# NRF52840-Beacon-V-1-3.net
KiCad netlist of a schematic drawn in Altium Designer
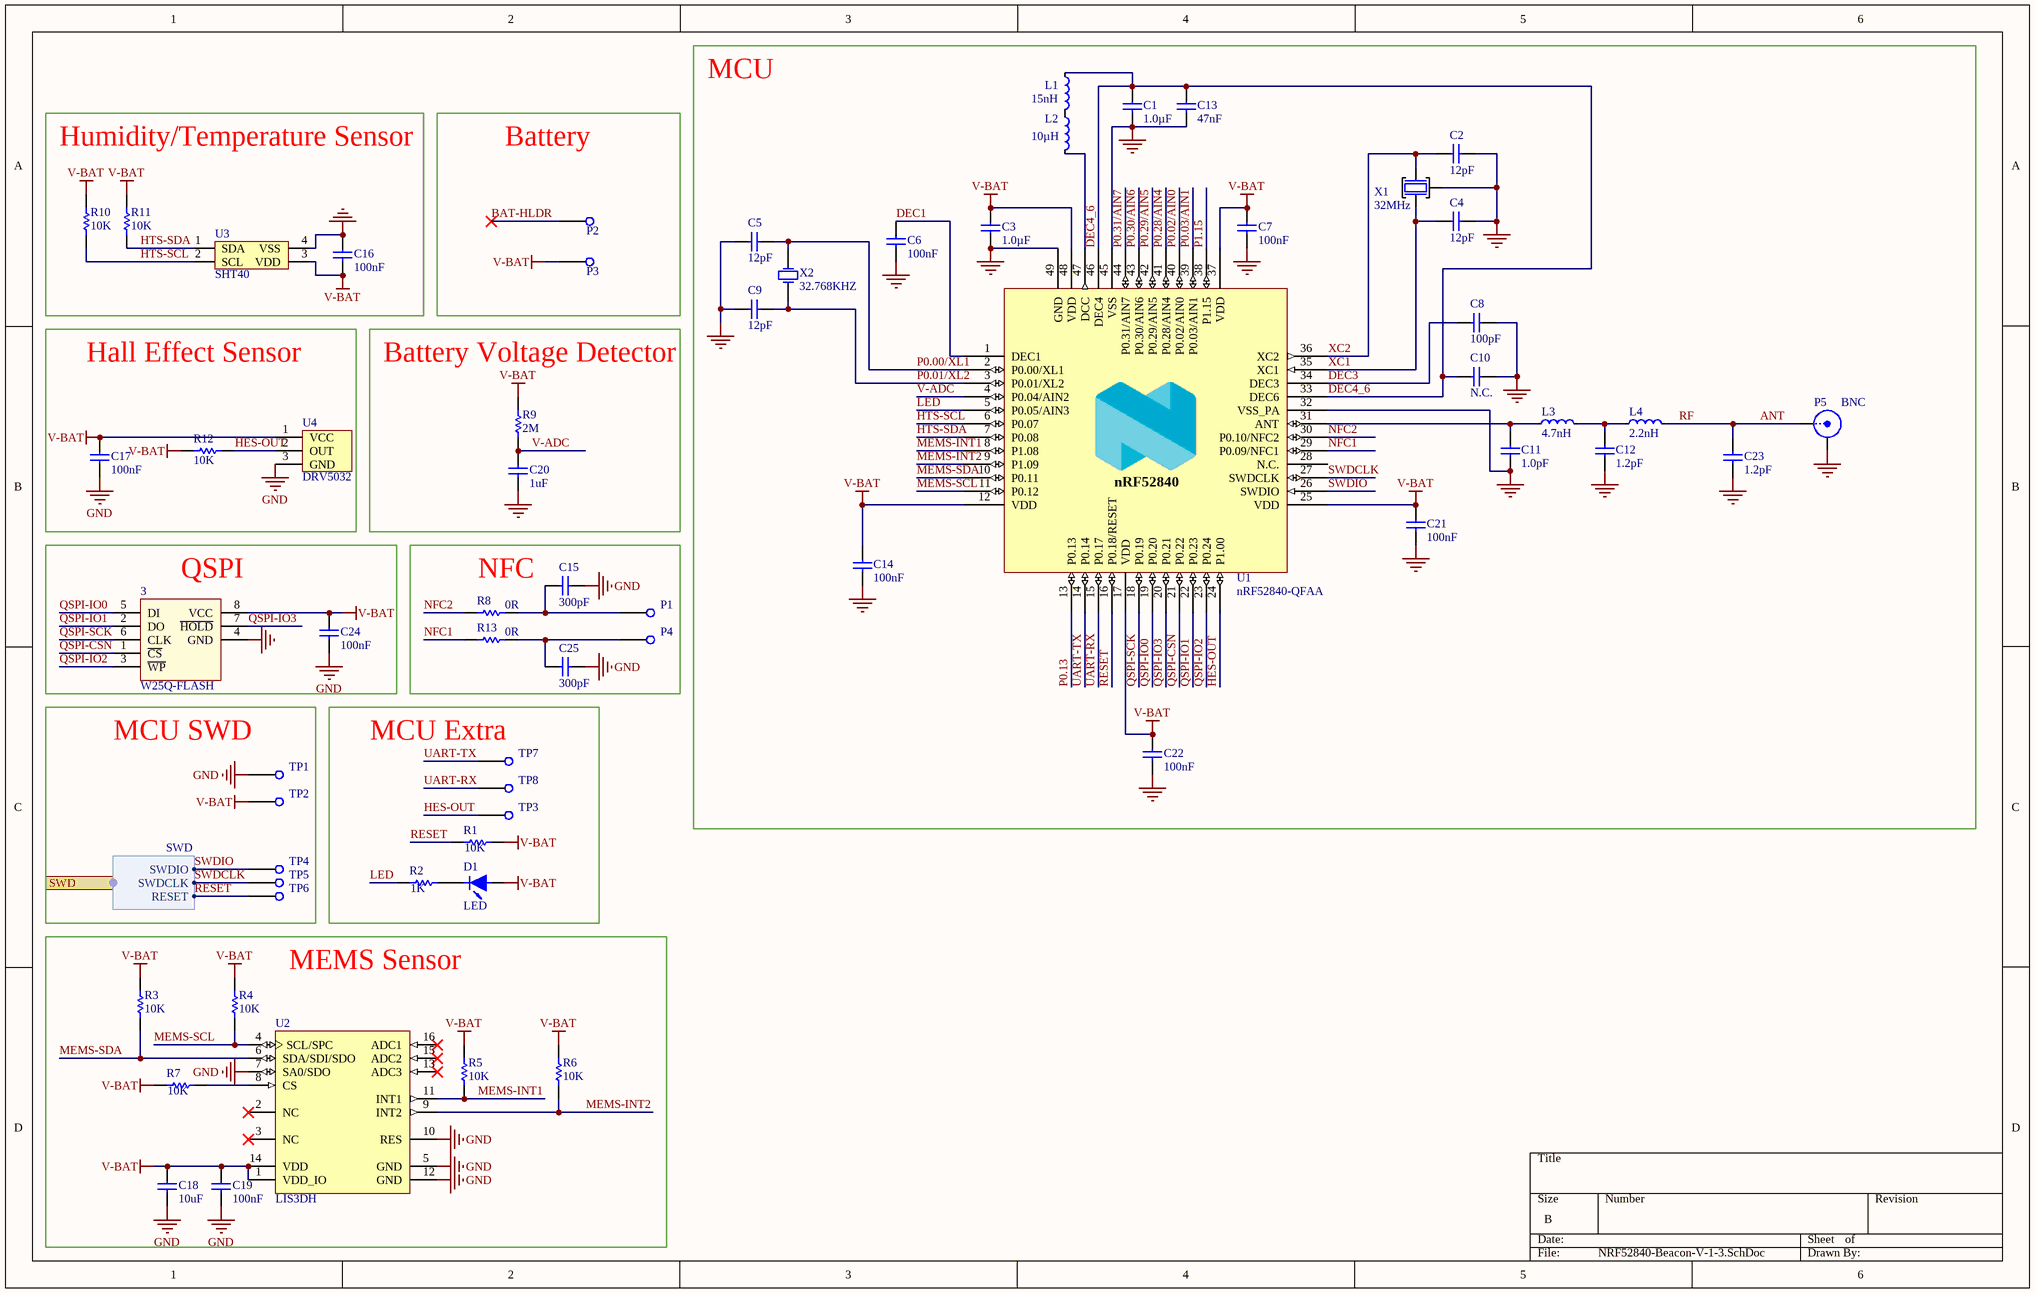
[diagram p0: NRF52840-Beacon-V-1-3.SchDoc]

(export (version "E")
  (design (tool "Eeschema 10.0.6"))
  (components
    (comp (ref "3")
      (value "W25Q-FLASH")
      (footprint "SO8W_M")
      (libsource (lib "My Devices") (part "W25Q-FLASH"))
    )
    (comp (ref "C1")
      (value "1.0µF")
      (footprint "CAPC1608N")
      (description "Capacitor, X5R, ±10%")
      (fields (field (name "PART NUMBER") "C0402-1µ0"))
      (libsource (lib "AltiumLib") (part "CAP"))
    )
    (comp (ref "C2")
      (value "12pF")
      (footprint "CAPC1608N")
      (description "Capacitor, NP0, ±2%")
      (fields (field (name "PART NUMBER") "C0201-12p"))
      (libsource (lib "AltiumLib") (part "CAP"))
    )
    (comp (ref "C3")
      (value "1.0µF")
      (footprint "CAPC1608N")
      (description "Capacitor, X5R, ±10%")
      (fields (field (name "PART NUMBER") "C0402-1µ0"))
      (libsource (lib "AltiumLib") (part "CAP"))
    )
    (comp (ref "C4")
      (value "12pF")
      (footprint "CAPC1608N")
      (description "Capacitor, NP0, ±2%")
      (fields (field (name "PART NUMBER") "C0201-12p"))
      (libsource (lib "AltiumLib") (part "CAP"))
    )
    (comp (ref "C5")
      (value "12pF")
      (footprint "CAPC1608N")
      (description "Capacitor, NP0, ±2%")
      (fields (field (name "PART NUMBER") "C0201-12p"))
      (libsource (lib "AltiumLib") (part "CAP"))
    )
    (comp (ref "C6")
      (value "100nF")
      (footprint "CAPC1608N")
      (description "Capacitor, X5R, ±10%")
      (fields (field (name "PART NUMBER") "C0201-100n"))
      (libsource (lib "AltiumLib") (part "CAP"))
    )
    (comp (ref "C7")
      (value "100nF")
      (footprint "CAPC1608N")
      (description "Capacitor, X5R, ±10%")
      (fields (field (name "PART NUMBER") "C0201-100n"))
      (libsource (lib "AltiumLib") (part "CAP"))
    )
    (comp (ref "C8")
      (value "100pF")
      (footprint "CAPC1608N")
      (description "Capacitor, NP0, ±5%")
      (fields (field (name "PART NUMBER") "C0201-100p"))
      (libsource (lib "AltiumLib") (part "CAP"))
    )
    (comp (ref "C9")
      (value "12pF")
      (footprint "CAPC1608N")
      (description "Capacitor, NP0, ±2%")
      (fields (field (name "PART NUMBER") "C0201-12p"))
      (libsource (lib "AltiumLib") (part "CAP"))
    )
    (comp (ref "C10")
      (value "N.C.")
      (footprint "CAPC1608N")
      (description "Not mounted")
      (fields (field (name "PART NUMBER") "C0201-N.C."))
      (libsource (lib "AltiumLib") (part "CAP"))
    )
    (comp (ref "C11")
      (value "1.0pF")
      (footprint "CAPC1608N")
      (description "Capacitor, NP0, ±10%")
      (fields (field (name "PART NUMBER") "C0201-1.0p"))
      (libsource (lib "AltiumLib") (part "CAP"))
    )
    (comp (ref "C12")
      (value "1.2pF")
      (footprint "CAPC1608N")
      (description "Capacitor, NP0, ±10%")
      (fields (field (name "PART NUMBER") "C0201-1.2p"))
      (libsource (lib "AltiumLib") (part "CAP"))
    )
    (comp (ref "C13")
      (value "47nF")
      (footprint "CAPC1608N")
      (description "Capacitor, X5R, ±10%")
      (fields (field (name "PART NUMBER") "C0201-47n"))
      (libsource (lib "AltiumLib") (part "CAP"))
    )
    (comp (ref "C14")
      (value "100nF")
      (footprint "CAPC1608N")
      (description "Capacitor, X5R, ±10%")
      (fields (field (name "PART NUMBER") "C0201-100n"))
      (libsource (lib "AltiumLib") (part "CAP"))
    )
    (comp (ref "C15")
      (value "300pF")
      (footprint "CAPC1608N")
      (description "Capacitor, NP0, ±2%")
      (fields (field (name "PART NUMBER") "C0201-12p"))
      (libsource (lib "AltiumLib") (part "CAP"))
    )
    (comp (ref "C16")
      (value "100nF")
      (footprint "CAPC1608N")
      (description "Capacitor, NP0, ±2%")
      (fields (field (name "PART NUMBER") "C0201-12p"))
      (libsource (lib "AltiumLib") (part "CAP"))
    )
    (comp (ref "C17")
      (value "100nF")
      (footprint "CAPC1608N")
      (description "Capacitor, NP0, ±2%")
      (fields (field (name "PART NUMBER") "C0201-12p"))
      (libsource (lib "AltiumLib") (part "CAP"))
    )
    (comp (ref "C18")
      (value "10uF")
      (footprint "CAPC1608N")
      (description "Capacitor, NP0, ±2%")
      (fields (field (name "PART NUMBER") "C0201-12p"))
      (libsource (lib "AltiumLib") (part "CAP"))
    )
    (comp (ref "C19")
      (value "100nF")
      (footprint "CAPC1608N")
      (description "Capacitor, NP0, ±2%")
      (fields (field (name "PART NUMBER") "C0201-12p"))
      (libsource (lib "AltiumLib") (part "CAP"))
    )
    (comp (ref "C20")
      (value "1uF")
      (footprint "CAPC1608N")
      (description "Capacitor, NP0, ±2%")
      (fields (field (name "PART NUMBER") "C0201-12p"))
      (libsource (lib "AltiumLib") (part "CAP"))
    )
    (comp (ref "C21")
      (value "100nF")
      (footprint "CAPC1608N")
      (description "Capacitor, X5R, ±10%")
      (fields (field (name "PART NUMBER") "C0201-100n"))
      (libsource (lib "AltiumLib") (part "CAP"))
    )
    (comp (ref "C22")
      (value "100nF")
      (footprint "CAPC1608N")
      (description "Capacitor, X5R, ±10%")
      (fields (field (name "PART NUMBER") "C0201-100n"))
      (libsource (lib "AltiumLib") (part "CAP"))
    )
    (comp (ref "C23")
      (value "1.2pF")
      (footprint "CAPC1608N")
      (description "Capacitor, NP0, ±10%")
      (fields (field (name "PART NUMBER") "C0201-1.2p"))
      (libsource (lib "AltiumLib") (part "CAP"))
    )
    (comp (ref "C24")
      (value "100nF")
      (footprint "CAPC1608N")
      (description "Capacitor, NP0, ±2%")
      (fields (field (name "PART NUMBER") "C0201-12p"))
      (libsource (lib "AltiumLib") (part "CAP"))
    )
    (comp (ref "C25")
      (value "300pF")
      (footprint "CAPC1608N")
      (description "Capacitor, NP0, ±2%")
      (fields (field (name "PART NUMBER") "C0201-12p"))
      (libsource (lib "AltiumLib") (part "CAP"))
    )
    (comp (ref "D1")
      (value "LED")
      (footprint "LED_0603")
      (fields (field (name "PUBLISHER") "Altium Limited"))
      (libsource (lib "My Devices") (part "LED"))
    )
    (comp (ref "L1")
      (value "15nH")
      (footprint "INDC1608N")
      (description "High frequency chip inductor ±10%")
      (fields (field (name "PART NUMBER") "L0402-15n"))
      (libsource (lib "AltiumLib") (part "IND"))
    )
    (comp (ref "L2")
      (value "10µH")
      (footprint "INDC1608N")
      (description "Chip inductor, IDC,min = 50 mA, ±20%")
      (fields (field (name "PART NUMBER") "L0603-10µ-TDK"))
      (libsource (lib "AltiumLib") (part "IND"))
    )
    (comp (ref "L3")
      (value "4.7nH")
      (footprint "INDC1608N")
      (description "High frequency chip inductor ±5%")
      (fields (field (name "PART NUMBER") "L0201-4n7"))
      (libsource (lib "AltiumLib") (part "IND"))
    )
    (comp (ref "L4")
      (value "2.2nH")
      (footprint "INDC1608N")
      (description "High frequency chip inductor ±5%")
      (fields (field (name "PART NUMBER") "L0201-2n2"))
      (libsource (lib "AltiumLib") (part "IND"))
    )
    (comp (ref "P1") (value "PIN") (footprint "PIN") (libsource (lib "My Connectors") (part "PIN")))
    (comp (ref "P2") (value "PIN") (footprint "PIN") (libsource (lib "My Connectors") (part "PIN")))
    (comp (ref "P3") (value "PIN") (footprint "PIN") (libsource (lib "My Connectors") (part "PIN")))
    (comp (ref "P4") (value "PIN") (footprint "PIN") (libsource (lib "My Connectors") (part "PIN")))
    (comp (ref "P5")
      (value "BNC")
      (footprint "UFL-Connector")
      (description "Coaxial Connector")
      (fields (field (name "PUBLISHER") "Altium Limited"))
      (libsource (lib "My Connectors") (part "BNC"))
    )
    (comp (ref "R1") (value "10K") (footprint "RESC1608N") (libsource (lib "My Devices") (part "Resistor")))
    (comp (ref "R2") (value "1K") (footprint "RESC1608N") (libsource (lib "My Devices") (part "Resistor")))
    (comp (ref "R3") (value "10K") (footprint "RESC1608N") (libsource (lib "My Devices") (part "Resistor")))
    (comp (ref "R4") (value "10K") (footprint "RESC1608N") (libsource (lib "My Devices") (part "Resistor")))
    (comp (ref "R5") (value "10K") (footprint "RESC1608N") (libsource (lib "My Devices") (part "Resistor")))
    (comp (ref "R6") (value "10K") (footprint "RESC1608N") (libsource (lib "My Devices") (part "Resistor")))
    (comp (ref "R7") (value "10K") (footprint "RESC1608N") (libsource (lib "My Devices") (part "Resistor")))
    (comp (ref "R8") (value "0R") (footprint "RESC1608N") (libsource (lib "My Devices") (part "Resistor")))
    (comp (ref "R9") (value "2M") (footprint "RESC1608N") (libsource (lib "My Devices") (part "Resistor")))
    (comp (ref "R10") (value "10K") (footprint "RESC1608N") (libsource (lib "My Devices") (part "Resistor")))
    (comp (ref "R11") (value "10K") (footprint "RESC1608N") (libsource (lib "My Devices") (part "Resistor")))
    (comp (ref "R12") (value "10K") (footprint "RESC1608N") (libsource (lib "My Devices") (part "Resistor")))
    (comp (ref "R13") (value "0R") (footprint "RESC1608N") (libsource (lib "My Devices") (part "Resistor")))
    (comp (ref "TP1") (value "PIN") (footprint "PIN") (libsource (lib "My Connectors") (part "PIN")))
    (comp (ref "TP2") (value "PIN") (footprint "PIN") (libsource (lib "My Connectors") (part "PIN")))
    (comp (ref "TP3") (value "PIN") (footprint "PIN") (libsource (lib "My Connectors") (part "PIN")))
    (comp (ref "TP4") (value "PIN") (footprint "PIN") (libsource (lib "My Connectors") (part "PIN")))
    (comp (ref "TP5") (value "PIN") (footprint "PIN") (libsource (lib "My Connectors") (part "PIN")))
    (comp (ref "TP6") (value "PIN") (footprint "PIN") (libsource (lib "My Connectors") (part "PIN")))
    (comp (ref "TP7") (value "PIN") (footprint "PIN") (libsource (lib "My Connectors") (part "PIN")))
    (comp (ref "TP8") (value "PIN") (footprint "PIN") (libsource (lib "My Connectors") (part "PIN")))
    (comp (ref "U1")
      (value "nRF52840-QFAA")
      (footprint "QFN40P600X600X90-48N")
      (description "Multi-protocol Bluetooth Low Energy, IEEE 802.15.4, ANT and 2.4GHz proprietary system-on-chip")
      (libsource (lib "AltiumLib") (part "nRF52840_QFAA"))
    )
    (comp (ref "U2")
      (value "LIS3DH")
      (footprint "LGA-16")
      (fields (field (name "MANUFACTURER") "STMicroelectronics"))
      (libsource (lib "My Devices") (part "LIS3DH"))
    )
    (comp (ref "U3")
      (value "SHT40")
      (footprint "SHT40")
      (description "High-Accuracy, Ultra-Low-Power, 16-bit, Relative Humidity and Temperature Sensor")
      (libsource (lib "My Devices") (part "SHT40"))
    )
    (comp (ref "U4")
      (value "DRV5032")
      (footprint "SOT-23")
      (description "ultra-low-power digital-switch Hall effect sensor")
      (libsource (lib "My Devices") (part "Hall_Effect_Sensor_Switch"))
    )
    (comp (ref "X1")
      (value "32MHz")
      (footprint "CRYSTAL_2016_NT")
      (description "XTAL SMD 2016, 32MHz, Cl=8pF, Total Tol: ±30ppm")
      (fields (field (name "PART NUMBER") "XTAL_SMD2016_32MHz_8pF_General_NT"))
      (libsource (lib "AltiumLib") (part "XTAL_4-pin_NT"))
    )
    (comp (ref "X2")
      (value "32.768KHZ")
      (footprint "CRYSTAL_3215")
      (libsource (lib "My Devices") (part "Crystal_Oscillator_2PIN"))
    )
  )
  (nets
    (net (code "2") (name "/ANT") (class "Default")
      (node (ref "C23") (pin "1") (pinfunction "1_1") (pintype "passive"))
      (node (ref "L4") (pin "2") (pinfunction "2_2") (pintype "passive"))
      (node (ref "P5") (pin "SIG") (pinfunction "SIG_SIG") (pintype "passive"))
    )
    (net (code "3") (name "/BAT-HLDR") (class "Default")
      (node (ref "P2") (pin "1") (pinfunction "PIN_1") (pintype "passive+no_connect"))
    )
    (net (code "4") (name "/DEC1") (class "Default")
      (node (ref "C6") (pin "1") (pinfunction "1_1") (pintype "passive"))
      (node (ref "U1") (pin "1") (pinfunction "DEC1_1") (pintype "power_in"))
    )
    (net (code "5") (name "/DEC3") (class "Default")
      (node (ref "C8") (pin "1") (pinfunction "1_1") (pintype "passive"))
      (node (ref "U1") (pin "34") (pinfunction "DEC3_34") (pintype "power_in"))
    )
    (net (code "6") (name "/DEC4_6") (class "Default")
      (node (ref "C1") (pin "2") (pinfunction "2_2") (pintype "passive"))
      (node (ref "C10") (pin "2") (pinfunction "2_2") (pintype "passive"))
      (node (ref "C13") (pin "1") (pinfunction "1_1") (pintype "passive"))
      (node (ref "L1") (pin "1") (pinfunction "1_1") (pintype "passive"))
      (node (ref "U1") (pin "33") (pinfunction "DEC6_33") (pintype "power_in"))
      (node (ref "U1") (pin "46") (pinfunction "DEC4_46") (pintype "power_in"))
    )
    (net (code "7") (name "/HES-OUT") (class "Default")
      (node (ref "R12") (pin "2") (pinfunction "2_2") (pintype "passive"))
      (node (ref "TP3") (pin "1") (pinfunction "PIN_1") (pintype "passive"))
      (node (ref "U1") (pin "24") (pinfunction "P1.00_24") (pintype "bidirectional"))
      (node (ref "U4") (pin "2") (pinfunction "OUT_2") (pintype "passive"))
    )
    (net (code "8") (name "/HTS-SCL") (class "Default")
      (node (ref "R10") (pin "2") (pinfunction "2_2") (pintype "passive"))
      (node (ref "U1") (pin "6") (pinfunction "P0.07_6") (pintype "bidirectional"))
      (node (ref "U3") (pin "2") (pinfunction "SCL_2") (pintype "passive"))
    )
    (net (code "9") (name "/HTS-SDA") (class "Default")
      (node (ref "R11") (pin "2") (pinfunction "2_2") (pintype "passive"))
      (node (ref "U1") (pin "7") (pinfunction "P0.08_7") (pintype "bidirectional"))
      (node (ref "U3") (pin "1") (pinfunction "SDA_1") (pintype "passive"))
    )
    (net (code "10") (name "/LED") (class "Default")
      (node (ref "R2") (pin "1") (pinfunction "1_1") (pintype "passive"))
      (node (ref "U1") (pin "5") (pinfunction "P0.05/AIN3_5") (pintype "bidirectional"))
    )
    (net (code "11") (name "/MEMS-INT1") (class "Default")
      (node (ref "R5") (pin "2") (pinfunction "2_2") (pintype "passive"))
      (node (ref "U1") (pin "8") (pinfunction "P1.08_8") (pintype "bidirectional"))
      (node (ref "U2") (pin "11") (pinfunction "INT1_11") (pintype "output"))
    )
    (net (code "12") (name "/MEMS-INT2") (class "Default")
      (node (ref "R6") (pin "2") (pinfunction "2_2") (pintype "passive"))
      (node (ref "U1") (pin "9") (pinfunction "P1.09_9") (pintype "bidirectional"))
      (node (ref "U2") (pin "9") (pinfunction "INT2_9") (pintype "output"))
    )
    (net (code "13") (name "/MEMS-SCL") (class "Default")
      (node (ref "R4") (pin "2") (pinfunction "2_2") (pintype "passive"))
      (node (ref "U1") (pin "11") (pinfunction "P0.12_11") (pintype "bidirectional"))
      (node (ref "U2") (pin "4") (pinfunction "SCL/SPC_4") (pintype "bidirectional"))
    )
    (net (code "14") (name "/MEMS-SDA") (class "Default")
      (node (ref "R3") (pin "2") (pinfunction "2_2") (pintype "passive"))
      (node (ref "U1") (pin "10") (pinfunction "P0.11_10") (pintype "bidirectional"))
      (node (ref "U2") (pin "6") (pinfunction "SDA/SDI/SDO_6") (pintype "bidirectional"))
    )
    (net (code "15") (name "/NFC1") (class "Default")
      (node (ref "R13") (pin "2") (pinfunction "2_2") (pintype "passive"))
      (node (ref "U1") (pin "29") (pinfunction "P0.09/NFC1_29") (pintype "bidirectional"))
    )
    (net (code "16") (name "/NFC2") (class "Default")
      (node (ref "R8") (pin "2") (pinfunction "2_2") (pintype "passive"))
      (node (ref "U1") (pin "30") (pinfunction "P0.10/NFC2_30") (pintype "bidirectional"))
    )
    (net (code "17") (name "/P0.00{slash}XL1") (class "Default")
      (node (ref "C5") (pin "1") (pinfunction "1_1") (pintype "passive"))
      (node (ref "U1") (pin "2") (pinfunction "P0.00/XL1_2") (pintype "bidirectional"))
      (node (ref "X2") (pin "2") (pinfunction "OSC2_2") (pintype "passive"))
    )
    (net (code "18") (name "/P0.01{slash}XL2") (class "Default")
      (node (ref "C9") (pin "1") (pinfunction "1_1") (pintype "passive"))
      (node (ref "U1") (pin "3") (pinfunction "P0.01/XL2_3") (pintype "bidirectional"))
      (node (ref "X2") (pin "1") (pinfunction "OSC1_1") (pintype "passive"))
    )
    (net (code "19") (name "/P0.02{slash}AIN0") (class "Default")
      (node (ref "U1") (pin "40") (pinfunction "P0.02/AIN0_40") (pintype "bidirectional"))
    )
    (net (code "20") (name "/P0.03{slash}AIN1") (class "Default")
      (node (ref "U1") (pin "39") (pinfunction "P0.03/AIN1_39") (pintype "bidirectional"))
    )
    (net (code "21") (name "/P0.13") (class "Default")
      (node (ref "U1") (pin "13") (pinfunction "P0.13_13") (pintype "bidirectional"))
    )
    (net (code "22") (name "/P0.28{slash}AIN4") (class "Default")
      (node (ref "U1") (pin "41") (pinfunction "P0.28/AIN4_41") (pintype "bidirectional"))
    )
    (net (code "23") (name "/P0.29{slash}AIN5") (class "Default")
      (node (ref "U1") (pin "42") (pinfunction "P0.29/AIN5_42") (pintype "bidirectional"))
    )
    (net (code "24") (name "/P0.30{slash}AIN6") (class "Default")
      (node (ref "U1") (pin "43") (pinfunction "P0.30/AIN6_43") (pintype "bidirectional"))
    )
    (net (code "25") (name "/P0.31{slash}AIN7") (class "Default")
      (node (ref "U1") (pin "44") (pinfunction "P0.31/AIN7_44") (pintype "bidirectional"))
    )
    (net (code "26") (name "/P1.15") (class "Default")
      (node (ref "U1") (pin "38") (pinfunction "P1.15_38") (pintype "bidirectional"))
    )
    (net (code "27") (name "/QSPI-CSN") (class "Default")
      (node (ref "3") (pin "1") (pinfunction "~{CS}_1") (pintype "passive"))
      (node (ref "U1") (pin "21") (pinfunction "P0.22_21") (pintype "bidirectional"))
    )
    (net (code "28") (name "/QSPI-IO0") (class "Default")
      (node (ref "3") (pin "5") (pinfunction "DI_5") (pintype "passive"))
      (node (ref "U1") (pin "19") (pinfunction "P0.20_19") (pintype "bidirectional"))
    )
    (net (code "29") (name "/QSPI-IO1") (class "Default")
      (node (ref "3") (pin "2") (pinfunction "DO_2") (pintype "passive"))
      (node (ref "U1") (pin "22") (pinfunction "P0.23_22") (pintype "bidirectional"))
    )
    (net (code "30") (name "/QSPI-IO2") (class "Default")
      (node (ref "3") (pin "3") (pinfunction "~{WP}_3") (pintype "passive"))
      (node (ref "U1") (pin "23") (pinfunction "P0.24_23") (pintype "bidirectional"))
    )
    (net (code "31") (name "/QSPI-IO3") (class "Default")
      (node (ref "3") (pin "7") (pinfunction "~{HOLD}_7") (pintype "passive"))
      (node (ref "U1") (pin "20") (pinfunction "P0.21_20") (pintype "bidirectional"))
    )
    (net (code "32") (name "/QSPI-SCK") (class "Default")
      (node (ref "3") (pin "6") (pinfunction "CLK_6") (pintype "passive"))
      (node (ref "U1") (pin "18") (pinfunction "P0.19_18") (pintype "bidirectional"))
    )
    (net (code "33") (name "/RESET") (class "Default")
      (node (ref "R1") (pin "1") (pinfunction "1_1") (pintype "passive"))
      (node (ref "TP6") (pin "1") (pinfunction "PIN_1") (pintype "passive"))
      (node (ref "U1") (pin "16") (pinfunction "P0.18/RESET_16") (pintype "bidirectional"))
    )
    (net (code "34") (name "/SWDCLK") (class "Default")
      (node (ref "TP5") (pin "1") (pinfunction "PIN_1") (pintype "passive"))
      (node (ref "U1") (pin "27") (pinfunction "SWDCLK_27") (pintype "bidirectional"))
    )
    (net (code "35") (name "/SWDIO") (class "Default")
      (node (ref "TP4") (pin "1") (pinfunction "PIN_1") (pintype "passive"))
      (node (ref "U1") (pin "26") (pinfunction "SWDIO_26") (pintype "input"))
    )
    (net (code "36") (name "/UART-RX") (class "Default")
      (node (ref "TP8") (pin "1") (pinfunction "PIN_1") (pintype "passive"))
      (node (ref "U1") (pin "15") (pinfunction "P0.17_15") (pintype "bidirectional"))
    )
    (net (code "37") (name "/UART-TX") (class "Default")
      (node (ref "TP7") (pin "1") (pinfunction "PIN_1") (pintype "passive"))
      (node (ref "U1") (pin "14") (pinfunction "P0.14_14") (pintype "bidirectional"))
    )
    (net (code "38") (name "/V-ADC") (class "Default")
      (node (ref "C20") (pin "1") (pinfunction "1_1") (pintype "passive"))
      (node (ref "R9") (pin "1") (pinfunction "1_1") (pintype "passive"))
      (node (ref "U1") (pin "4") (pinfunction "P0.04/AIN2_4") (pintype "bidirectional"))
    )
    (net (code "39") (name "/XC1") (class "Default")
      (node (ref "C4") (pin "1") (pinfunction "1_1") (pintype "passive"))
      (node (ref "U1") (pin "35") (pinfunction "XC1_35") (pintype "input"))
      (node (ref "X1") (pin "1") (pinfunction "IN_1") (pintype "passive"))
    )
    (net (code "40") (name "/XC2") (class "Default")
      (node (ref "C2") (pin "1") (pinfunction "1_1") (pintype "passive"))
      (node (ref "U1") (pin "36") (pinfunction "XC2_36") (pintype "output"))
      (node (ref "X1") (pin "3") (pinfunction "OUT_3") (pintype "passive"))
    )
    (net (code "42") (name "GND") (class "Default")
      (node (ref "3") (pin "4") (pinfunction "GND_4") (pintype "passive"))
      (node (ref "C1") (pin "1") (pinfunction "1_1") (pintype "passive"))
      (node (ref "C10") (pin "1") (pinfunction "1_1") (pintype "passive"))
      (node (ref "C11") (pin "1") (pinfunction "1_1") (pintype "passive"))
      (node (ref "C12") (pin "1") (pinfunction "1_1") (pintype "passive"))
      (node (ref "C13") (pin "2") (pinfunction "2_2") (pintype "passive"))
      (node (ref "C14") (pin "2") (pinfunction "2_2") (pintype "passive"))
      (node (ref "C15") (pin "2") (pinfunction "2_2") (pintype "passive"))
      (node (ref "C16") (pin "1") (pinfunction "1_1") (pintype "passive"))
      (node (ref "C17") (pin "2") (pinfunction "2_2") (pintype "passive"))
      (node (ref "C18") (pin "2") (pinfunction "2_2") (pintype "passive"))
      (node (ref "C19") (pin "2") (pinfunction "2_2") (pintype "passive"))
      (node (ref "C2") (pin "2") (pinfunction "2_2") (pintype "passive"))
      (node (ref "C20") (pin "2") (pinfunction "2_2") (pintype "passive"))
      (node (ref "C21") (pin "2") (pinfunction "2_2") (pintype "passive"))
      (node (ref "C22") (pin "2") (pinfunction "2_2") (pintype "passive"))
      (node (ref "C23") (pin "2") (pinfunction "2_2") (pintype "passive"))
      (node (ref "C24") (pin "2") (pinfunction "2_2") (pintype "passive"))
      (node (ref "C25") (pin "2") (pinfunction "2_2") (pintype "passive"))
      (node (ref "C3") (pin "2") (pinfunction "2_2") (pintype "passive"))
      (node (ref "C4") (pin "2") (pinfunction "2_2") (pintype "passive"))
      (node (ref "C5") (pin "2") (pinfunction "2_2") (pintype "passive"))
      (node (ref "C6") (pin "2") (pinfunction "2_2") (pintype "passive"))
      (node (ref "C7") (pin "2") (pinfunction "2_2") (pintype "passive"))
      (node (ref "C8") (pin "2") (pinfunction "2_2") (pintype "passive"))
      (node (ref "C9") (pin "2") (pinfunction "2_2") (pintype "passive"))
      (node (ref "P5") (pin "GND") (pinfunction "GNDY_GND") (pintype "passive"))
      (node (ref "TP1") (pin "1") (pinfunction "PIN_1") (pintype "passive"))
      (node (ref "U1") (pin "32") (pinfunction "VSS_PA_32") (pintype "power_in"))
      (node (ref "U1") (pin "45") (pinfunction "VSS_45") (pintype "power_in"))
      (node (ref "U1") (pin "49") (pinfunction "GND_49") (pintype "power_in"))
      (node (ref "U2") (pin "10") (pinfunction "RES_10") (pintype "power_in"))
      (node (ref "U2") (pin "12") (pinfunction "GND_12") (pintype "power_in"))
      (node (ref "U2") (pin "5") (pinfunction "GND_5") (pintype "power_in"))
      (node (ref "U2") (pin "7") (pinfunction "SA0/SDO_7") (pintype "bidirectional"))
      (node (ref "U3") (pin "4") (pinfunction "VSS_4") (pintype "passive"))
      (node (ref "U4") (pin "3") (pinfunction "GND_3") (pintype "passive"))
      (node (ref "X1") (pin "2") (pinfunction "GND_2") (pintype "passive"))
    )
    (net (code "43") (name "Net-(C12-Pad2)") (class "Default")
      (node (ref "C12") (pin "2") (pinfunction "2_2") (pintype "passive"))
      (node (ref "L3") (pin "2") (pinfunction "2_2") (pintype "passive"))
      (node (ref "L4") (pin "1") (pinfunction "1_1") (pintype "passive"))
    )
    (net (code "44") (name "Net-(D1-K)") (class "Default")
      (node (ref "D1") (pin "2") (pinfunction "K_2") (pintype "passive"))
      (node (ref "R2") (pin "2") (pinfunction "2_2") (pintype "passive"))
    )
    (net (code "45") (name "Net-(L1-Pad2)") (class "Default")
      (node (ref "L1") (pin "2") (pinfunction "2_2") (pintype "passive"))
      (node (ref "L2") (pin "1") (pinfunction "1_1") (pintype "passive"))
    )
    (net (code "46") (name "Net-(P1-PIN)") (class "Default")
      (node (ref "C15") (pin "1") (pinfunction "1_1") (pintype "passive"))
      (node (ref "P1") (pin "1") (pinfunction "PIN_1") (pintype "passive"))
      (node (ref "R8") (pin "1") (pinfunction "1_1") (pintype "passive"))
    )
    (net (code "47") (name "Net-(P4-PIN)") (class "Default")
      (node (ref "C25") (pin "1") (pinfunction "1_1") (pintype "passive"))
      (node (ref "P4") (pin "1") (pinfunction "PIN_1") (pintype "passive"))
      (node (ref "R13") (pin "1") (pinfunction "1_1") (pintype "passive"))
    )
    (net (code "48") (name "Net-(U1-ANT)") (class "Default")
      (node (ref "C11") (pin "2") (pinfunction "2_2") (pintype "passive"))
      (node (ref "L3") (pin "1") (pinfunction "1_1") (pintype "passive"))
      (node (ref "U1") (pin "31") (pinfunction "ANT_31") (pintype "bidirectional"))
    )
    (net (code "49") (name "Net-(U1-DCC)") (class "Default")
      (node (ref "L2") (pin "2") (pinfunction "2_2") (pintype "passive"))
      (node (ref "U1") (pin "47") (pinfunction "DCC_47") (pintype "output"))
    )
    (net (code "50") (name "Net-(U2-CS)") (class "Default")
      (node (ref "R7") (pin "2") (pinfunction "2_2") (pintype "passive"))
      (node (ref "U2") (pin "8") (pinfunction "CS_8") (pintype "input"))
    )
    (net (code "51") (name "V-BAT") (class "Default")
      (node (ref "3") (pin "8") (pinfunction "VCC_8") (pintype "passive"))
      (node (ref "C14") (pin "1") (pinfunction "1_1") (pintype "passive"))
      (node (ref "C16") (pin "2") (pinfunction "2_2") (pintype "passive"))
      (node (ref "C17") (pin "1") (pinfunction "1_1") (pintype "passive"))
      (node (ref "C18") (pin "1") (pinfunction "1_1") (pintype "passive"))
      (node (ref "C19") (pin "1") (pinfunction "1_1") (pintype "passive"))
      (node (ref "C21") (pin "1") (pinfunction "1_1") (pintype "passive"))
      (node (ref "C22") (pin "1") (pinfunction "1_1") (pintype "passive"))
      (node (ref "C24") (pin "1") (pinfunction "1_1") (pintype "passive"))
      (node (ref "C3") (pin "1") (pinfunction "1_1") (pintype "passive"))
      (node (ref "C7") (pin "1") (pinfunction "1_1") (pintype "passive"))
      (node (ref "D1") (pin "1") (pinfunction "A_1") (pintype "passive"))
      (node (ref "P3") (pin "1") (pinfunction "PIN_1") (pintype "passive"))
      (node (ref "R1") (pin "2") (pinfunction "2_2") (pintype "passive"))
      (node (ref "R10") (pin "1") (pinfunction "1_1") (pintype "passive"))
      (node (ref "R11") (pin "1") (pinfunction "1_1") (pintype "passive"))
      (node (ref "R12") (pin "1") (pinfunction "1_1") (pintype "passive"))
      (node (ref "R3") (pin "1") (pinfunction "1_1") (pintype "passive"))
      (node (ref "R4") (pin "1") (pinfunction "1_1") (pintype "passive"))
      (node (ref "R5") (pin "1") (pinfunction "1_1") (pintype "passive"))
      (node (ref "R6") (pin "1") (pinfunction "1_1") (pintype "passive"))
      (node (ref "R7") (pin "1") (pinfunction "1_1") (pintype "passive"))
      (node (ref "R9") (pin "2") (pinfunction "2_2") (pintype "passive"))
      (node (ref "TP2") (pin "1") (pinfunction "PIN_1") (pintype "passive"))
      (node (ref "U1") (pin "12") (pinfunction "VDD_12") (pintype "power_in"))
      (node (ref "U1") (pin "17") (pinfunction "VDD_17") (pintype "power_in"))
      (node (ref "U1") (pin "25") (pinfunction "VDD_25") (pintype "power_in"))
      (node (ref "U1") (pin "37") (pinfunction "VDD_37") (pintype "power_in"))
      (node (ref "U1") (pin "48") (pinfunction "VDD_48") (pintype "power_in"))
      (node (ref "U2") (pin "1") (pinfunction "VDD_IO_1") (pintype "power_in"))
      (node (ref "U2") (pin "14") (pinfunction "VDD_14") (pintype "power_in"))
      (node (ref "U3") (pin "3") (pinfunction "VDD_3") (pintype "passive"))
      (node (ref "U4") (pin "1") (pinfunction "VCC_1") (pintype "passive"))
    )
    (net (code "52") (name "unconnected-(U1-N.C.-Pad28)") (class "Default")
      (node (ref "U1") (pin "28") (pinfunction "N.C._28") (pintype "passive"))
    )
    (net (code "53") (name "unconnected-(U2-ADC1-Pad16)") (class "Default")
      (node (ref "U2") (pin "16") (pinfunction "ADC1_16") (pintype "input+no_connect"))
    )
    (net (code "54") (name "unconnected-(U2-ADC2-Pad15)") (class "Default")
      (node (ref "U2") (pin "15") (pinfunction "ADC2_15") (pintype "input+no_connect"))
    )
    (net (code "55") (name "unconnected-(U2-ADC3-Pad13)") (class "Default")
      (node (ref "U2") (pin "13") (pinfunction "ADC3_13") (pintype "input+no_connect"))
    )
    (net (code "56") (name "unconnected-(U2-NC-Pad2)") (class "Default")
      (node (ref "U2") (pin "2") (pinfunction "NC_2") (pintype "passive+no_connect"))
    )
    (net (code "57") (name "unconnected-(U2-NC-Pad3)") (class "Default")
      (node (ref "U2") (pin "3") (pinfunction "NC_3") (pintype "passive+no_connect"))
    )
  )
)
